# dgainblock.net
KiCad netlist of a schematic drawn in Altium Designer
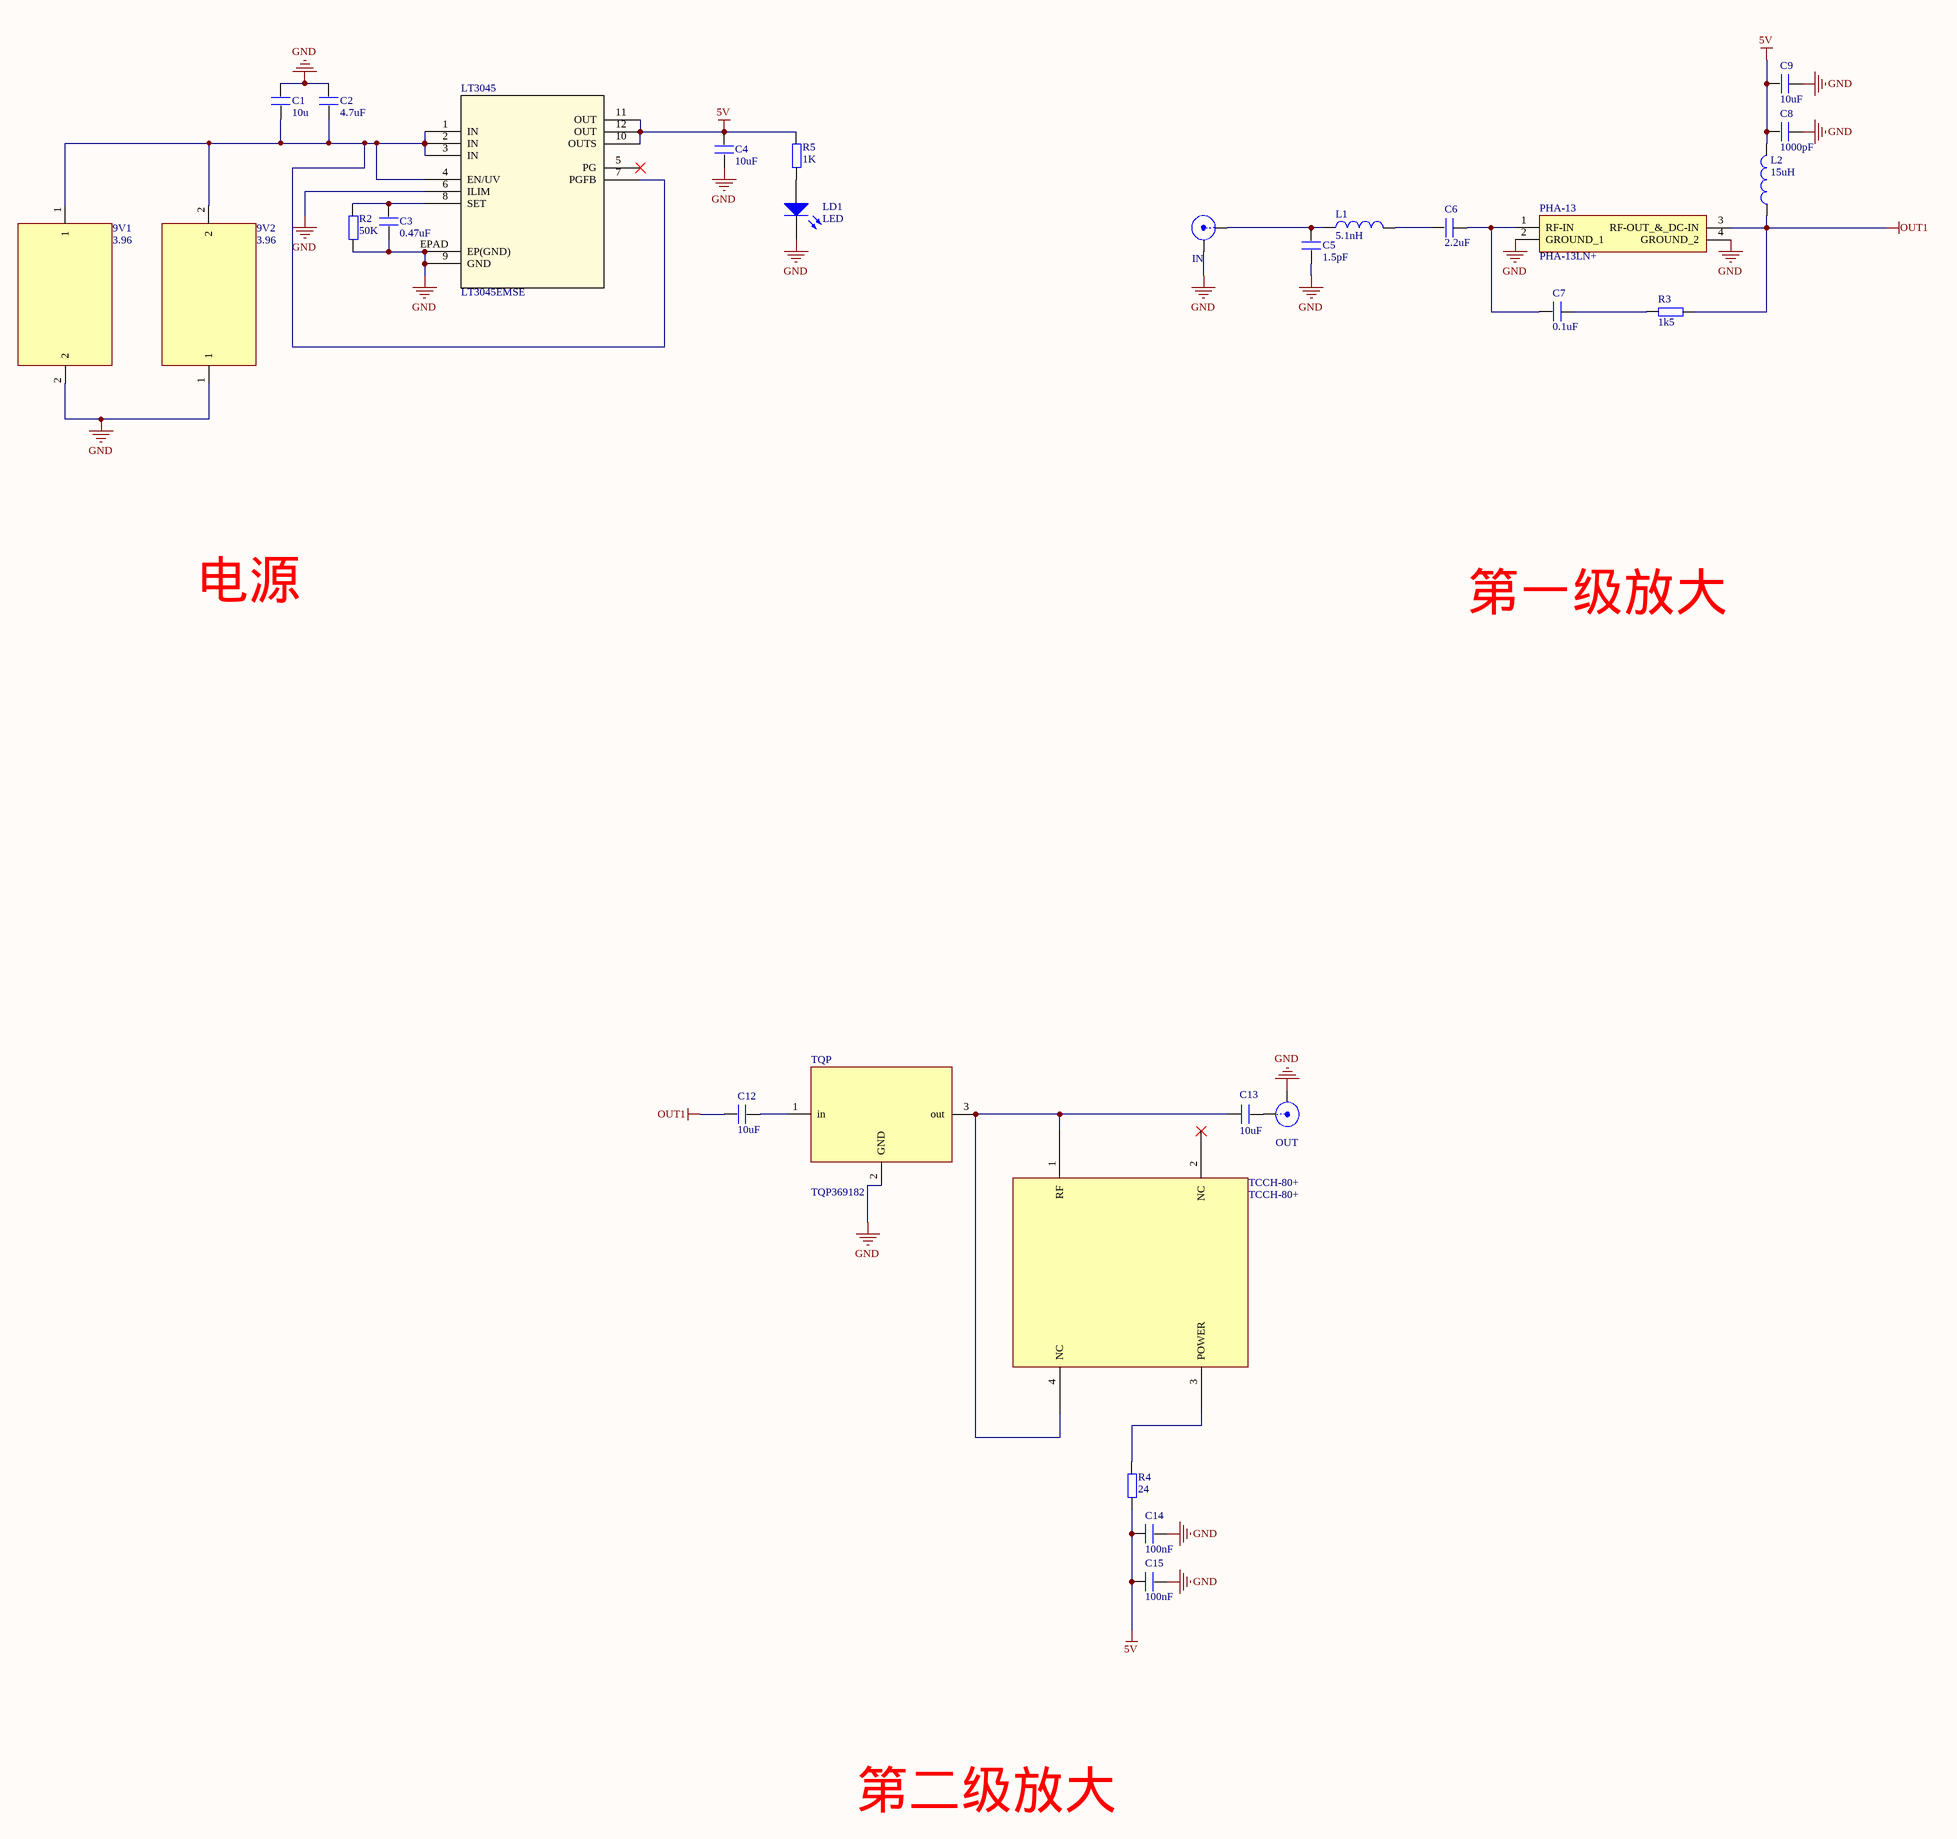
[diagram p0: dgainblock.SchDoc]

(export (version "E")
  (design (tool "Eeschema 10.0.6"))
  (components
    (comp (ref "9V1") (value "3.96") (footprint "3.96") (libsource (lib "MYLIB") (part "3.96")))
    (comp (ref "9V2") (value "3.96") (footprint "3.96") (libsource (lib "") (part "3.96_1")))
    (comp (ref "C1")
      (value "10u")
      (footprint "0603C")
      (description "Capacitor")
      (libsource (lib "MYLIB") (part "C"))
    )
    (comp (ref "C2")
      (value "4.7uF")
      (footprint "0603C")
      (description "Capacitor")
      (libsource (lib "MYLIB") (part "C"))
    )
    (comp (ref "C3")
      (value "0.47uF")
      (footprint "0402")
      (description "Capacitor")
      (libsource (lib "MYLIB") (part "C"))
    )
    (comp (ref "C4")
      (value "10uF")
      (footprint "0402")
      (description "Capacitor")
      (libsource (lib "MYLIB") (part "C"))
    )
    (comp (ref "C5")
      (value "1.5pF")
      (footprint "0402")
      (description "Capacitor")
      (libsource (lib "MYLIB") (part "C"))
    )
    (comp (ref "C6")
      (value "2.2uF")
      (footprint "0402")
      (description "Capacitor")
      (libsource (lib "MYLIB") (part "C"))
    )
    (comp (ref "C7")
      (value "0.1uF")
      (footprint "0402")
      (description "Capacitor")
      (libsource (lib "MYLIB") (part "C"))
    )
    (comp (ref "C8")
      (value "1000pF")
      (footprint "0402")
      (description "Capacitor")
      (libsource (lib "MYLIB") (part "C"))
    )
    (comp (ref "C9")
      (value "10uF")
      (footprint "0603C")
      (description "Capacitor")
      (libsource (lib "MYLIB") (part "C"))
    )
    (comp (ref "C12")
      (value "10uF")
      (footprint "0402")
      (description "Capacitor")
      (libsource (lib "MYLIB") (part "C"))
    )
    (comp (ref "C13")
      (value "10uF")
      (footprint "0402")
      (description "Capacitor")
      (libsource (lib "MYLIB") (part "C"))
    )
    (comp (ref "C14")
      (value "100nF")
      (footprint "0603C")
      (description "Capacitor")
      (libsource (lib "MYLIB") (part "C"))
    )
    (comp (ref "C15")
      (value "100nF")
      (footprint "0603C")
      (description "Capacitor")
      (libsource (lib "MYLIB") (part "C"))
    )
    (comp (ref "IN")
      (value "SMA")
      (footprint "SMA")
      (description "SMA Connector")
      (libsource (lib "MYLIB") (part "SMA"))
    )
    (comp (ref "L1")
      (value "5.1nH")
      (footprint "0402")
      (description "Inductor")
      (fields (field (name "PUBLISHER") "Altium Limited"))
      (libsource (lib "MYLIB") (part "Inductor"))
    )
    (comp (ref "L2")
      (value "15uH")
      (footprint "C1210-L")
      (description "Inductor")
      (fields (field (name "PUBLISHER") "Altium Limited"))
      (libsource (lib "MYLIB") (part "Inductor"))
    )
    (comp (ref "LD1")
      (value "LED")
      (footprint "SMDLED")
      (description "Typical RED, GREEN, YELLOW, AMBER GaAs LED")
      (fields (field (name "PUBLISHER") "Altium Limited"))
      (libsource (lib "MYLIB") (part "LED"))
    )
    (comp (ref "LT3045")
      (value "LT3045EMSE")
      (footprint "MSOP12-MSE-RevG_ADI")
      (description "No Description Available")
      (fields (field (name "COPYRIGHT") "Copyright (C) 2018 Accelerated Designs. All rights reserved"))
      (libsource (lib "MYLIB") (part "LT3045EMSE"))
    )
    (comp (ref "OUT")
      (value "SMA")
      (footprint "SMA")
      (description "SMA Connector")
      (libsource (lib "MYLIB") (part "SMA"))
    )
    (comp (ref "PHA-13")
      (value "PHA-13LN+")
      (footprint "MYLIB:PHA13LN")
      (description "Integrated Circuit")
      (fields (field (name "MOUSER PART NUMBER") "139-PHA-13LN"))
      (libsource (lib "*") (part "PHA-13LN+"))
    )
    (comp (ref "R2")
      (value "50K")
      (footprint "0402")
      (description "Resistor")
      (libsource (lib "MYLIB") (part "Resistor"))
    )
    (comp (ref "R3")
      (value "1k5")
      (footprint "0402")
      (description "Resistor")
      (libsource (lib "MYLIB") (part "Resistor"))
    )
    (comp (ref "R4")
      (value "24")
      (footprint "1206")
      (description "Resistor")
      (libsource (lib "MYLIB") (part "Resistor"))
    )
    (comp (ref "R5")
      (value "1K")
      (footprint "0603R")
      (description "Resistor")
      (libsource (lib "MYLIB") (part "Resistor"))
    )
    (comp (ref "TCCH-80+")
      (value "TCCH-80+")
      (footprint "GU1604")
      (libsource (lib "MYLIB") (part "TCCH-80+"))
    )
    (comp (ref "TQP") (value "TQP369182") (footprint "SOT89_M") (libsource (lib "MYLIB") (part "TQP369182")))
  )
  (nets
    (net (code "1") (name "5V") (class "Default")
      (node (ref "C14") (pin "1") (pintype "passive"))
      (node (ref "C15") (pin "1") (pintype "passive"))
      (node (ref "C4") (pin "2") (pintype "passive"))
      (node (ref "C8") (pin "2") (pintype "passive"))
      (node (ref "C9") (pin "2") (pintype "passive"))
      (node (ref "L2") (pin "2") (pinfunction "2_2") (pintype "passive"))
      (node (ref "LT3045") (pin "10") (pinfunction "OUTS_10") (pintype "passive"))
      (node (ref "LT3045") (pin "11") (pinfunction "OUT_11") (pintype "passive"))
      (node (ref "LT3045") (pin "12") (pinfunction "OUT_12") (pintype "passive"))
      (node (ref "R4") (pin "1") (pintype "passive"))
      (node (ref "R5") (pin "2") (pintype "passive"))
    )
    (net (code "2") (name "GND") (class "Default")
      (node (ref "9V1") (pin "2") (pinfunction "2_2") (pintype "passive"))
      (node (ref "9V2") (pin "1") (pinfunction "1_1") (pintype "passive"))
      (node (ref "C1") (pin "2") (pintype "passive"))
      (node (ref "C14") (pin "2") (pintype "passive"))
      (node (ref "C15") (pin "2") (pintype "passive"))
      (node (ref "C2") (pin "2") (pintype "passive"))
      (node (ref "C3") (pin "1") (pintype "passive"))
      (node (ref "C4") (pin "1") (pintype "passive"))
      (node (ref "C5") (pin "1") (pintype "passive"))
      (node (ref "C8") (pin "1") (pintype "passive"))
      (node (ref "C9") (pin "1") (pintype "passive"))
      (node (ref "IN") (pin "2") (pinfunction "Y_2") (pintype "passive"))
      (node (ref "LD1") (pin "2") (pinfunction "K_2") (pintype "passive"))
      (node (ref "LT3045") (pin "6") (pinfunction "ILIM_6") (pintype "passive"))
      (node (ref "LT3045") (pin "9") (pinfunction "GND_9") (pintype "passive"))
      (node (ref "LT3045") (pin "EPAD") (pinfunction "EP(GND)_EPAD") (pintype "passive"))
      (node (ref "OUT") (pin "2") (pinfunction "Y_2") (pintype "passive"))
      (node (ref "PHA-13") (pin "2") (pinfunction "GROUND_1_2") (pintype "passive"))
      (node (ref "PHA-13") (pin "4") (pinfunction "GROUND_2_4") (pintype "passive"))
      (node (ref "R2") (pin "1") (pintype "passive"))
      (node (ref "TQP") (pin "2") (pinfunction "GND_2") (pintype "passive"))
    )
    (net (code "3") (name "Net-(C6-Pad2)") (class "Default")
      (node (ref "C6") (pin "2") (pintype "passive"))
      (node (ref "L1") (pin "2") (pinfunction "2_2") (pintype "passive"))
    )
    (net (code "4") (name "Net-(C7-Pad1)") (class "Default")
      (node (ref "C7") (pin "1") (pintype "passive"))
      (node (ref "R3") (pin "1") (pintype "passive"))
    )
    (net (code "5") (name "Net-(IN-X)") (class "Default")
      (node (ref "C5") (pin "2") (pintype "passive"))
      (node (ref "IN") (pin "1") (pinfunction "X_1") (pintype "passive"))
      (node (ref "L1") (pin "1") (pinfunction "1_1") (pintype "passive"))
    )
    (net (code "6") (name "Net-(LD1-A)") (class "Default")
      (node (ref "LD1") (pin "1") (pinfunction "A_1") (pintype "passive"))
      (node (ref "R5") (pin "1") (pintype "passive"))
    )
    (net (code "7") (name "Net-(LT3045-EN{slash}UV)") (class "Default")
      (node (ref "9V1") (pin "1") (pinfunction "1_1") (pintype "passive"))
      (node (ref "9V2") (pin "2") (pinfunction "2_2") (pintype "passive"))
      (node (ref "C1") (pin "1") (pintype "passive"))
      (node (ref "C2") (pin "1") (pintype "passive"))
      (node (ref "LT3045") (pin "1") (pinfunction "IN_1") (pintype "passive"))
      (node (ref "LT3045") (pin "2") (pinfunction "IN_2") (pintype "passive"))
      (node (ref "LT3045") (pin "3") (pinfunction "IN_3") (pintype "passive"))
      (node (ref "LT3045") (pin "4") (pinfunction "EN/UV_4") (pintype "passive"))
      (node (ref "LT3045") (pin "7") (pinfunction "PGFB_7") (pintype "passive"))
    )
    (net (code "8") (name "Net-(LT3045-SET)") (class "Default")
      (node (ref "C3") (pin "2") (pintype "passive"))
      (node (ref "LT3045") (pin "8") (pinfunction "SET_8") (pintype "passive"))
      (node (ref "R2") (pin "2") (pintype "passive"))
    )
    (net (code "9") (name "Net-(OUT-X)") (class "Default")
      (node (ref "C13") (pin "2") (pintype "passive"))
      (node (ref "OUT") (pin "1") (pinfunction "X_1") (pintype "passive"))
    )
    (net (code "10") (name "Net-(PHA-13-RF-IN)") (class "Default")
      (node (ref "C6") (pin "1") (pintype "passive"))
      (node (ref "C7") (pin "2") (pintype "passive"))
      (node (ref "PHA-13") (pin "1") (pinfunction "RF-IN_1") (pintype "passive"))
    )
    (net (code "11") (name "Net-(TCCH-80+-POWER)") (class "Default")
      (node (ref "R4") (pin "2") (pintype "passive"))
      (node (ref "TCCH-80+") (pin "3") (pinfunction "POWER_3") (pintype "passive"))
    )
    (net (code "12") (name "Net-(TCCH-80+-RF)") (class "Default")
      (node (ref "C13") (pin "1") (pintype "passive"))
      (node (ref "TCCH-80+") (pin "1") (pinfunction "RF_1") (pintype "passive"))
      (node (ref "TCCH-80+") (pin "4") (pinfunction "NC_4") (pintype "passive"))
      (node (ref "TQP") (pin "3") (pinfunction "out_3") (pintype "passive"))
    )
    (net (code "13") (name "Net-(TQP-in)") (class "Default")
      (node (ref "C12") (pin "2") (pintype "passive"))
      (node (ref "TQP") (pin "1") (pinfunction "in_1") (pintype "passive"))
    )
    (net (code "14") (name "OUT1") (class "Default")
      (node (ref "C12") (pin "1") (pintype "passive"))
      (node (ref "L2") (pin "1") (pinfunction "1_1") (pintype "passive"))
      (node (ref "PHA-13") (pin "3") (pinfunction "RF-OUT_&_DC-IN_3") (pintype "passive"))
      (node (ref "R3") (pin "2") (pintype "passive"))
    )
    (net (code "15") (name "unconnected-(LT3045-PG-Pad5)") (class "Default")
      (node (ref "LT3045") (pin "5") (pinfunction "PG_5") (pintype "passive+no_connect"))
    )
    (net (code "16") (name "unconnected-(TCCH-80+-NC-Pad2)") (class "Default")
      (node (ref "TCCH-80+") (pin "2") (pinfunction "NC_2") (pintype "passive+no_connect"))
    )
  )
)
